# MainBorad_ver2_1.net
KiCad netlist of a schematic drawn in EAGLE
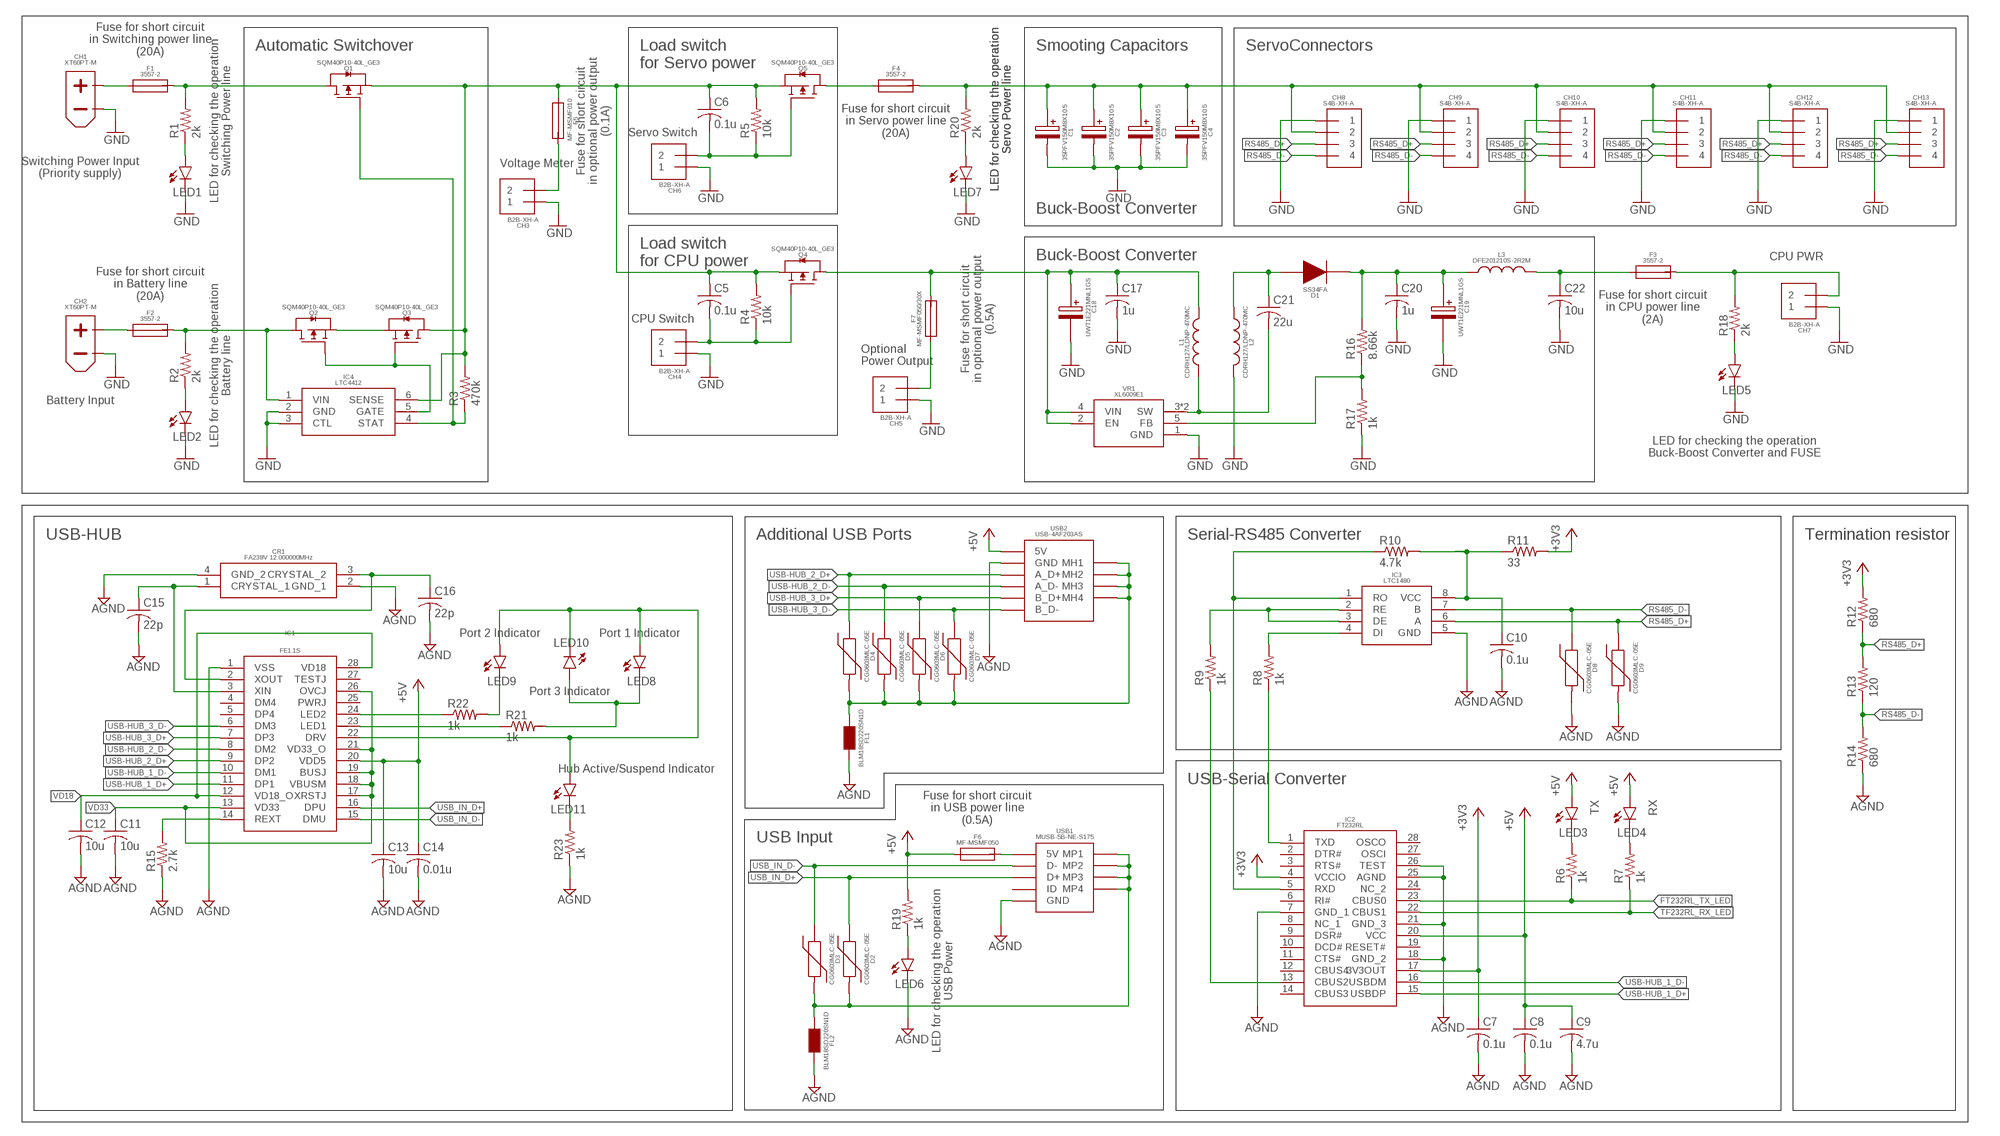
[diagram p0: schematic, sheet 1]

(export (version "E")
  (design (tool "Eeschema 10.0.6"))
  (components
    (comp (ref "C1")
      (value "35PFV150M8X10.5")
      (footprint "eagle-import:35PFV150M8X10.5")
      (libsource (lib "eagle-import") (part "35PFV150M8X10.5"))
    )
    (comp (ref "C2")
      (value "35PFV150M8X10.5")
      (footprint "eagle-import:35PFV150M8X10.5")
      (libsource (lib "eagle-import") (part "35PFV150M8X10.5"))
    )
    (comp (ref "C3")
      (value "35PFV150M8X10.5")
      (footprint "eagle-import:35PFV150M8X10.5")
      (libsource (lib "eagle-import") (part "35PFV150M8X10.5"))
    )
    (comp (ref "C4")
      (value "35PFV150M8X10.5")
      (footprint "eagle-import:35PFV150M8X10.5")
      (libsource (lib "eagle-import") (part "35PFV150M8X10.5"))
    )
    (comp (ref "C5")
      (value "0.1u")
      (footprint "eagle-import:C0603")
      (libsource (lib "eagle-import") (part "C-USC0603"))
    )
    (comp (ref "C6")
      (value "0.1u")
      (footprint "eagle-import:C0603")
      (libsource (lib "eagle-import") (part "C-USC0603"))
    )
    (comp (ref "C7")
      (value "0.1u")
      (footprint "eagle-import:C0603")
      (libsource (lib "eagle-import") (part "C-USC0603"))
    )
    (comp (ref "C8")
      (value "0.1u")
      (footprint "eagle-import:C0603")
      (libsource (lib "eagle-import") (part "C-USC0603"))
    )
    (comp (ref "C9")
      (value "4.7u")
      (footprint "eagle-import:C0603")
      (libsource (lib "eagle-import") (part "C-USC0603"))
    )
    (comp (ref "C10")
      (value "0.1u")
      (footprint "eagle-import:C0603")
      (libsource (lib "eagle-import") (part "C-USC0603"))
    )
    (comp (ref "C11")
      (value "10u")
      (footprint "eagle-import:C0603")
      (libsource (lib "eagle-import") (part "C-USC0603"))
    )
    (comp (ref "C12")
      (value "10u")
      (footprint "eagle-import:C0603")
      (libsource (lib "eagle-import") (part "C-USC0603"))
    )
    (comp (ref "C13")
      (value "10u")
      (footprint "eagle-import:C0603")
      (libsource (lib "eagle-import") (part "C-USC0603"))
    )
    (comp (ref "C14")
      (value "0.01u")
      (footprint "eagle-import:C0603")
      (libsource (lib "eagle-import") (part "C-USC0603"))
    )
    (comp (ref "C15")
      (value "22p")
      (footprint "eagle-import:C0603")
      (libsource (lib "eagle-import") (part "C-USC0603"))
    )
    (comp (ref "C16")
      (value "22p")
      (footprint "eagle-import:C0603")
      (libsource (lib "eagle-import") (part "C-USC0603"))
    )
    (comp (ref "C17")
      (value "1u")
      (footprint "eagle-import:C0603")
      (libsource (lib "eagle-import") (part "C-USC0603"))
    )
    (comp (ref "C18")
      (value "UWT1E221MNL1GS")
      (footprint "eagle-import:UWT1E221MNL1GS")
      (libsource (lib "eagle-import") (part "UWT1E221MNL1GS"))
    )
    (comp (ref "C19")
      (value "UWT1E221MNL1GS")
      (footprint "eagle-import:UWT1E221MNL1GS")
      (libsource (lib "eagle-import") (part "UWT1E221MNL1GS"))
    )
    (comp (ref "C20")
      (value "1u")
      (footprint "eagle-import:C0603")
      (libsource (lib "eagle-import") (part "C-USC0603"))
    )
    (comp (ref "C21")
      (value "22u")
      (footprint "eagle-import:C2012")
      (libsource (lib "eagle-import") (part "C-USC2012"))
    )
    (comp (ref "C22")
      (value "10u")
      (footprint "eagle-import:C0603")
      (libsource (lib "eagle-import") (part "C-USC0603"))
    )
    (comp (ref "CH1")
      (value "XT60PT-M")
      (footprint "eagle-import:XT60PT-M")
      (libsource (lib "eagle-import") (part "XT60PT-M"))
    )
    (comp (ref "CH2")
      (value "XT60PT-M")
      (footprint "eagle-import:XT60PT-M")
      (libsource (lib "eagle-import") (part "XT60PT-M"))
    )
    (comp (ref "CH3")
      (value "B2B-XH-A")
      (footprint "eagle-import:B2B-XH-A")
      (libsource (lib "eagle-import") (part "B2B-XH-A"))
    )
    (comp (ref "CH4")
      (value "B2B-XH-A")
      (footprint "eagle-import:B2B-XH-A")
      (libsource (lib "eagle-import") (part "B2B-XH-A"))
    )
    (comp (ref "CH5")
      (value "B2B-XH-A")
      (footprint "eagle-import:B2B-XH-A")
      (libsource (lib "eagle-import") (part "B2B-XH-A"))
    )
    (comp (ref "CH6")
      (value "B2B-XH-A")
      (footprint "eagle-import:B2B-XH-A")
      (libsource (lib "eagle-import") (part "B2B-XH-A"))
    )
    (comp (ref "CH7")
      (value "B2B-XH-A")
      (footprint "eagle-import:B2B-XH-A")
      (libsource (lib "eagle-import") (part "B2B-XH-A"))
    )
    (comp (ref "CH8")
      (value "S4B-XH-A")
      (footprint "eagle-import:S4B-XH-A")
      (libsource (lib "eagle-import") (part "S4B-XH-A"))
    )
    (comp (ref "CH9")
      (value "S4B-XH-A")
      (footprint "eagle-import:S4B-XH-A")
      (libsource (lib "eagle-import") (part "S4B-XH-A"))
    )
    (comp (ref "CH10")
      (value "S4B-XH-A")
      (footprint "eagle-import:S4B-XH-A")
      (libsource (lib "eagle-import") (part "S4B-XH-A"))
    )
    (comp (ref "CH11")
      (value "S4B-XH-A")
      (footprint "eagle-import:S4B-XH-A")
      (libsource (lib "eagle-import") (part "S4B-XH-A"))
    )
    (comp (ref "CH12")
      (value "S4B-XH-A")
      (footprint "eagle-import:S4B-XH-A")
      (libsource (lib "eagle-import") (part "S4B-XH-A"))
    )
    (comp (ref "CH13")
      (value "S4B-XH-A")
      (footprint "eagle-import:S4B-XH-A")
      (libsource (lib "eagle-import") (part "S4B-XH-A"))
    )
    (comp (ref "CR1")
      (value "FA238V_12.000000MHZ")
      (footprint "eagle-import:FA238V")
      (libsource (lib "eagle-import") (part "FA238V_12.000000MHZ"))
    )
    (comp (ref "D1")
      (value "SS34FA")
      (footprint "eagle-import:SS34FA")
      (libsource (lib "eagle-import") (part "SS34FA"))
    )
    (comp (ref "D2")
      (value "CG0603MLC-05E")
      (footprint "eagle-import:CG0603MLC-05E")
      (libsource (lib "eagle-import") (part "CG0603MLC-05E"))
    )
    (comp (ref "D3")
      (value "CG0603MLC-05E")
      (footprint "eagle-import:CG0603MLC-05E")
      (libsource (lib "eagle-import") (part "CG0603MLC-05E"))
    )
    (comp (ref "D4")
      (value "CG0603MLC-05E")
      (footprint "eagle-import:CG0603MLC-05E")
      (libsource (lib "eagle-import") (part "CG0603MLC-05E"))
    )
    (comp (ref "D5")
      (value "CG0603MLC-05E")
      (footprint "eagle-import:CG0603MLC-05E")
      (libsource (lib "eagle-import") (part "CG0603MLC-05E"))
    )
    (comp (ref "D6")
      (value "CG0603MLC-05E")
      (footprint "eagle-import:CG0603MLC-05E")
      (libsource (lib "eagle-import") (part "CG0603MLC-05E"))
    )
    (comp (ref "D7")
      (value "CG0603MLC-05E")
      (footprint "eagle-import:CG0603MLC-05E")
      (libsource (lib "eagle-import") (part "CG0603MLC-05E"))
    )
    (comp (ref "D8")
      (value "CG0603MLC-05E")
      (footprint "eagle-import:CG0603MLC-05E")
      (libsource (lib "eagle-import") (part "CG0603MLC-05E"))
    )
    (comp (ref "D9")
      (value "CG0603MLC-05E")
      (footprint "eagle-import:CG0603MLC-05E")
      (libsource (lib "eagle-import") (part "CG0603MLC-05E"))
    )
    (comp (ref "F1")
      (value "3557-2")
      (footprint "eagle-import:3557-2")
      (libsource (lib "eagle-import") (part "3557-2"))
    )
    (comp (ref "F2")
      (value "3557-2")
      (footprint "eagle-import:3557-2")
      (libsource (lib "eagle-import") (part "3557-2"))
    )
    (comp (ref "F3")
      (value "3557-2")
      (footprint "eagle-import:3557-2")
      (libsource (lib "eagle-import") (part "3557-2"))
    )
    (comp (ref "F4")
      (value "3557-2")
      (footprint "eagle-import:3557-2")
      (libsource (lib "eagle-import") (part "3557-2"))
    )
    (comp (ref "F5")
      (value "MF-MSMF010")
      (footprint "eagle-import:MF-MSMF010")
      (libsource (lib "eagle-import") (part "MF-MSMF010"))
    )
    (comp (ref "F6")
      (value "MF-MSMF050")
      (footprint "eagle-import:MF-MSMF050")
      (libsource (lib "eagle-import") (part "MF-MSMF050"))
    )
    (comp (ref "F7")
      (value "MF-MSMF050/30X")
      (footprint "eagle-import:MF-MSMF050")
      (libsource (lib "eagle-import") (part "MF-MSMF050/30X"))
    )
    (comp (ref "FL1")
      (value "BLM18SD220SN1D")
      (footprint "eagle-import:BLM18SD220SN1D")
      (libsource (lib "eagle-import") (part "BLM18SD220SN1D"))
    )
    (comp (ref "FL2")
      (value "BLM18SD220SN1D")
      (footprint "eagle-import:BLM18SD220SN1D")
      (libsource (lib "eagle-import") (part "BLM18SD220SN1D"))
    )
    (comp (ref "IC1")
      (value "FE1.1S")
      (footprint "eagle-import:FE1.1S")
      (libsource (lib "eagle-import") (part "FE1.1S"))
    )
    (comp (ref "IC2")
      (value "FT232RL")
      (footprint "eagle-import:FT232RL")
      (libsource (lib "eagle-import") (part "FT232RL"))
    )
    (comp (ref "IC3")
      (value "LTC1480")
      (footprint "eagle-import:LTC1480")
      (libsource (lib "eagle-import") (part "LTC1480"))
    )
    (comp (ref "IC4")
      (value "LTC4412")
      (footprint "eagle-import:LTC4412")
      (libsource (lib "eagle-import") (part "LTC4412"))
    )
    (comp (ref "L1")
      (value "CDRH127/LDNP-470MC")
      (footprint "eagle-import:CDRH127_LDNP")
      (libsource (lib "eagle-import") (part "CDRH127/LDNP-470MC"))
    )
    (comp (ref "L2")
      (value "CDRH127/LDNP-470MC")
      (footprint "eagle-import:CDRH127_LDNP")
      (libsource (lib "eagle-import") (part "CDRH127/LDNP-470MC"))
    )
    (comp (ref "L3")
      (value "DFE201210S-2R2M")
      (footprint "eagle-import:DFE201210S")
      (libsource (lib "eagle-import") (part "DFE201210S-2R2M"))
    )
    (comp (ref "LED1")
      (value "LEDSML0603")
      (footprint "eagle-import:SML0603")
      (libsource (lib "eagle-import") (part "LEDSML0603"))
    )
    (comp (ref "LED2")
      (value "LEDSML0603")
      (footprint "eagle-import:SML0603")
      (libsource (lib "eagle-import") (part "LEDSML0603"))
    )
    (comp (ref "LED3")
      (value "LEDSML0603")
      (footprint "eagle-import:SML0603")
      (libsource (lib "eagle-import") (part "LEDSML0603"))
    )
    (comp (ref "LED4")
      (value "LEDSML0603")
      (footprint "eagle-import:SML0603")
      (libsource (lib "eagle-import") (part "LEDSML0603"))
    )
    (comp (ref "LED5")
      (value "LEDSML0603")
      (footprint "eagle-import:SML0603")
      (libsource (lib "eagle-import") (part "LEDSML0603"))
    )
    (comp (ref "LED6")
      (value "LEDSML0603")
      (footprint "eagle-import:SML0603")
      (libsource (lib "eagle-import") (part "LEDSML0603"))
    )
    (comp (ref "LED7")
      (value "LEDSML0603")
      (footprint "eagle-import:SML0603")
      (libsource (lib "eagle-import") (part "LEDSML0603"))
    )
    (comp (ref "LED8")
      (value "LEDSML0603")
      (footprint "eagle-import:SML0603")
      (libsource (lib "eagle-import") (part "LEDSML0603"))
    )
    (comp (ref "LED9")
      (value "LEDSML0603")
      (footprint "eagle-import:SML0603")
      (libsource (lib "eagle-import") (part "LEDSML0603"))
    )
    (comp (ref "LED10")
      (value "LEDSML0603")
      (footprint "eagle-import:SML0603")
      (libsource (lib "eagle-import") (part "LEDSML0603"))
    )
    (comp (ref "LED11")
      (value "LEDSML0603")
      (footprint "eagle-import:SML0603")
      (libsource (lib "eagle-import") (part "LEDSML0603"))
    )
    (comp (ref "Q1")
      (value "SQM40P10-40L_GE3")
      (footprint "eagle-import:TO-252-3")
      (libsource (lib "eagle-import") (part "SQM40P10-40L_GE3"))
    )
    (comp (ref "Q2")
      (value "SQM40P10-40L_GE3")
      (footprint "eagle-import:TO-252-3")
      (libsource (lib "eagle-import") (part "SQM40P10-40L_GE3"))
    )
    (comp (ref "Q3")
      (value "SQM40P10-40L_GE3")
      (footprint "eagle-import:TO-252-3")
      (libsource (lib "eagle-import") (part "SQM40P10-40L_GE3"))
    )
    (comp (ref "Q4")
      (value "SQM40P10-40L_GE3")
      (footprint "eagle-import:TO-252-3")
      (libsource (lib "eagle-import") (part "SQM40P10-40L_GE3"))
    )
    (comp (ref "Q5")
      (value "SQM40P10-40L_GE3")
      (footprint "eagle-import:TO-252-3")
      (libsource (lib "eagle-import") (part "SQM40P10-40L_GE3"))
    )
    (comp (ref "R1")
      (value "2k")
      (footprint "eagle-import:R0603")
      (libsource (lib "eagle-import") (part "R-US_R0603"))
    )
    (comp (ref "R2")
      (value "2k")
      (footprint "eagle-import:R0603")
      (libsource (lib "eagle-import") (part "R-US_R0603"))
    )
    (comp (ref "R3")
      (value "470k")
      (footprint "eagle-import:R0603")
      (libsource (lib "eagle-import") (part "R-US_R0603"))
    )
    (comp (ref "R4")
      (value "10k")
      (footprint "eagle-import:R0603")
      (libsource (lib "eagle-import") (part "R-US_R0603"))
    )
    (comp (ref "R5")
      (value "10k")
      (footprint "eagle-import:R0603")
      (libsource (lib "eagle-import") (part "R-US_R0603"))
    )
    (comp (ref "R6")
      (value "1k")
      (footprint "eagle-import:R0603")
      (libsource (lib "eagle-import") (part "R-US_R0603"))
    )
    (comp (ref "R7")
      (value "1k")
      (footprint "eagle-import:R0603")
      (libsource (lib "eagle-import") (part "R-US_R0603"))
    )
    (comp (ref "R8")
      (value "1k")
      (footprint "eagle-import:R0603")
      (libsource (lib "eagle-import") (part "R-US_R0603"))
    )
    (comp (ref "R9")
      (value "1k")
      (footprint "eagle-import:R0603")
      (libsource (lib "eagle-import") (part "R-US_R0603"))
    )
    (comp (ref "R10")
      (value "4.7k")
      (footprint "eagle-import:R0603")
      (libsource (lib "eagle-import") (part "R-US_R0603"))
    )
    (comp (ref "R11")
      (value "33")
      (footprint "eagle-import:R0603")
      (libsource (lib "eagle-import") (part "R-US_R0603"))
    )
    (comp (ref "R12")
      (value "680")
      (footprint "eagle-import:R0603")
      (libsource (lib "eagle-import") (part "R-US_R0603"))
    )
    (comp (ref "R13")
      (value "120")
      (footprint "eagle-import:R0603")
      (libsource (lib "eagle-import") (part "R-US_R0603"))
    )
    (comp (ref "R14")
      (value "680")
      (footprint "eagle-import:R0603")
      (libsource (lib "eagle-import") (part "R-US_R0603"))
    )
    (comp (ref "R15")
      (value "2.7k")
      (footprint "eagle-import:R0603")
      (libsource (lib "eagle-import") (part "R-US_R0603"))
    )
    (comp (ref "R16")
      (value "8.66k")
      (footprint "eagle-import:R0603")
      (libsource (lib "eagle-import") (part "R-US_R0603"))
    )
    (comp (ref "R17")
      (value "1k")
      (footprint "eagle-import:R0603")
      (libsource (lib "eagle-import") (part "R-US_R0603"))
    )
    (comp (ref "R18")
      (value "2k")
      (footprint "eagle-import:R0603")
      (libsource (lib "eagle-import") (part "R-US_R0603"))
    )
    (comp (ref "R19")
      (value "1k")
      (footprint "eagle-import:R0603")
      (libsource (lib "eagle-import") (part "R-US_R0603"))
    )
    (comp (ref "R20")
      (value "2k")
      (footprint "eagle-import:R0603")
      (libsource (lib "eagle-import") (part "R-US_R0603"))
    )
    (comp (ref "R21")
      (value "1k")
      (footprint "eagle-import:R0603")
      (libsource (lib "eagle-import") (part "R-US_R0603"))
    )
    (comp (ref "R22")
      (value "1k")
      (footprint "eagle-import:R0603")
      (libsource (lib "eagle-import") (part "R-US_R0603"))
    )
    (comp (ref "R23")
      (value "1k")
      (footprint "eagle-import:R0603")
      (libsource (lib "eagle-import") (part "R-US_R0603"))
    )
    (comp (ref "USB1")
      (value "MINI_USB_5P_B_TYPE")
      (footprint "eagle-import:MINI_USB_5P_B_TYPE")
      (libsource (lib "eagle-import") (part "MINI_USB_5P_B_TYPE"))
    )
    (comp (ref "USB2")
      (value "USB_4P_A_TYPE_X2")
      (footprint "eagle-import:USB_4P_A_TYPE_X2")
      (libsource (lib "eagle-import") (part "USB_4P_A_TYPE_X2"))
    )
    (comp (ref "VR1")
      (value "XL6009E1")
      (footprint "eagle-import:TO263-5L")
      (libsource (lib "eagle-import") (part "XL6009E1"))
    )
  )
  (nets
    (net (code "1") (name "+3V3") (class "Default")
      (node (ref "C7") (pin "1") (pinfunction "1_1") (pintype "passive"))
      (node (ref "IC2") (pin "17") (pinfunction "3V3OUT_17") (pintype "bidirectional"))
      (node (ref "IC2") (pin "4") (pinfunction "VCCIO_4") (pintype "bidirectional"))
      (node (ref "R11") (pin "2") (pinfunction "2_2") (pintype "passive"))
      (node (ref "R12") (pin "2") (pinfunction "2_2") (pintype "passive"))
    )
    (net (code "2") (name "+5V") (class "Default")
      (node (ref "C13") (pin "1") (pinfunction "1_1") (pintype "passive"))
      (node (ref "C14") (pin "1") (pinfunction "1_1") (pintype "passive"))
      (node (ref "C8") (pin "1") (pinfunction "1_1") (pintype "passive"))
      (node (ref "C9") (pin "1") (pinfunction "1_1") (pintype "passive"))
      (node (ref "F6") (pin "1") (pinfunction "1_1") (pintype "bidirectional"))
      (node (ref "IC1") (pin "20") (pinfunction "VDD5_20") (pintype "bidirectional"))
      (node (ref "IC2") (pin "20") (pinfunction "VCC_20") (pintype "bidirectional"))
      (node (ref "LED3") (pin "A") (pinfunction "A_A") (pintype "passive"))
      (node (ref "LED4") (pin "A") (pinfunction "A_A") (pintype "passive"))
      (node (ref "R19") (pin "2") (pinfunction "2_2") (pintype "passive"))
      (node (ref "USB2") (pin "4") (pinfunction "5V_4") (pintype "bidirectional"))
      (node (ref "USB2") (pin "8") (pinfunction "5V_8") (pintype "bidirectional"))
    )
    (net (code "3") (name "AGND") (class "Default")
      (node (ref "C10") (pin "2") (pinfunction "2_2") (pintype "passive"))
      (node (ref "C11") (pin "2") (pinfunction "2_2") (pintype "passive"))
      (node (ref "C12") (pin "2") (pinfunction "2_2") (pintype "passive"))
      (node (ref "C13") (pin "2") (pinfunction "2_2") (pintype "passive"))
      (node (ref "C14") (pin "2") (pinfunction "2_2") (pintype "passive"))
      (node (ref "C15") (pin "2") (pinfunction "2_2") (pintype "passive"))
      (node (ref "C16") (pin "2") (pinfunction "2_2") (pintype "passive"))
      (node (ref "C7") (pin "2") (pinfunction "2_2") (pintype "passive"))
      (node (ref "C8") (pin "2") (pinfunction "2_2") (pintype "passive"))
      (node (ref "C9") (pin "2") (pinfunction "2_2") (pintype "passive"))
      (node (ref "CR1") (pin "2") (pinfunction "GND_1_2") (pintype "bidirectional"))
      (node (ref "CR1") (pin "4") (pinfunction "GND_2_4") (pintype "bidirectional"))
      (node (ref "D8") (pin "2") (pinfunction "2_2") (pintype "bidirectional"))
      (node (ref "D9") (pin "2") (pinfunction "2_2") (pintype "bidirectional"))
      (node (ref "FL1") (pin "2") (pinfunction "2_2") (pintype "bidirectional"))
      (node (ref "FL2") (pin "2") (pinfunction "2_2") (pintype "bidirectional"))
      (node (ref "IC1") (pin "1") (pinfunction "VSS_1") (pintype "bidirectional"))
      (node (ref "IC2") (pin "18") (pinfunction "GND_2_18") (pintype "bidirectional"))
      (node (ref "IC2") (pin "21") (pinfunction "GND_3_21") (pintype "bidirectional"))
      (node (ref "IC2") (pin "25") (pinfunction "AGND_25") (pintype "bidirectional"))
      (node (ref "IC2") (pin "26") (pinfunction "TEST_26") (pintype "bidirectional"))
      (node (ref "IC2") (pin "7") (pinfunction "GND_1_7") (pintype "bidirectional"))
      (node (ref "IC3") (pin "5") (pinfunction "GND_5") (pintype "bidirectional"))
      (node (ref "LED6") (pin "C") (pinfunction "C_C") (pintype "passive"))
      (node (ref "R14") (pin "1") (pinfunction "1_1") (pintype "passive"))
      (node (ref "R15") (pin "1") (pinfunction "1_1") (pintype "passive"))
      (node (ref "R23") (pin "1") (pinfunction "1_1") (pintype "passive"))
      (node (ref "USB1") (pin "5") (pinfunction "GND_5") (pintype "bidirectional"))
      (node (ref "USB2") (pin "1") (pinfunction "GND_1") (pintype "bidirectional"))
      (node (ref "USB2") (pin "5") (pinfunction "GND_5") (pintype "bidirectional"))
    )
    (net (code "4") (name "FT232RL_TX_LED") (class "Default")
      (node (ref "IC2") (pin "23") (pinfunction "CBUS0_23") (pintype "bidirectional"))
      (node (ref "R6") (pin "1") (pinfunction "1_1") (pintype "passive"))
    )
    (net (code "5") (name "GND") (class "Default")
      (node (ref "C1") (pin "-") (pinfunction "-_-") (pintype "bidirectional"))
      (node (ref "C17") (pin "2") (pinfunction "2_2") (pintype "passive"))
      (node (ref "C18") (pin "-") (pinfunction "-_-") (pintype "bidirectional"))
      (node (ref "C19") (pin "-") (pinfunction "-_-") (pintype "bidirectional"))
      (node (ref "C2") (pin "-") (pinfunction "-_-") (pintype "bidirectional"))
      (node (ref "C20") (pin "2") (pinfunction "2_2") (pintype "passive"))
      (node (ref "C22") (pin "2") (pinfunction "2_2") (pintype "passive"))
      (node (ref "C3") (pin "-") (pinfunction "-_-") (pintype "bidirectional"))
      (node (ref "C4") (pin "-") (pinfunction "-_-") (pintype "bidirectional"))
      (node (ref "CH1") (pin "-") (pinfunction "-_-") (pintype "power_in"))
      (node (ref "CH10") (pin "1") (pinfunction "1_1") (pintype "bidirectional"))
      (node (ref "CH11") (pin "1") (pinfunction "1_1") (pintype "bidirectional"))
      (node (ref "CH12") (pin "1") (pinfunction "1_1") (pintype "bidirectional"))
      (node (ref "CH13") (pin "1") (pinfunction "1_1") (pintype "bidirectional"))
      (node (ref "CH2") (pin "-") (pinfunction "-_-") (pintype "power_in"))
      (node (ref "CH3") (pin "1") (pinfunction "1_1") (pintype "bidirectional"))
      (node (ref "CH4") (pin "1") (pinfunction "1_1") (pintype "bidirectional"))
      (node (ref "CH5") (pin "1") (pinfunction "1_1") (pintype "bidirectional"))
      (node (ref "CH6") (pin "1") (pinfunction "1_1") (pintype "bidirectional"))
      (node (ref "CH7") (pin "1") (pinfunction "1_1") (pintype "bidirectional"))
      (node (ref "CH8") (pin "1") (pinfunction "1_1") (pintype "bidirectional"))
      (node (ref "CH9") (pin "1") (pinfunction "1_1") (pintype "bidirectional"))
      (node (ref "IC4") (pin "2") (pinfunction "GND_2") (pintype "bidirectional"))
      (node (ref "IC4") (pin "3") (pinfunction "CTL_3") (pintype "bidirectional"))
      (node (ref "L2") (pin "2") (pinfunction "2_2") (pintype "bidirectional"))
      (node (ref "LED1") (pin "C") (pinfunction "C_C") (pintype "passive"))
      (node (ref "LED2") (pin "C") (pinfunction "C_C") (pintype "passive"))
      (node (ref "LED5") (pin "C") (pinfunction "C_C") (pintype "passive"))
      (node (ref "LED7") (pin "C") (pinfunction "C_C") (pintype "passive"))
      (node (ref "R17") (pin "1") (pinfunction "1_1") (pintype "passive"))
      (node (ref "VR1") (pin "1") (pinfunction "GND_1") (pintype "power_in"))
    )
    (net (code "6") (name "Net-(C1-Pad+)") (class "Default")
      (node (ref "C1") (pin "+") (pinfunction "+_+") (pintype "bidirectional"))
      (node (ref "C2") (pin "+") (pinfunction "+_+") (pintype "bidirectional"))
      (node (ref "C3") (pin "+") (pinfunction "+_+") (pintype "bidirectional"))
      (node (ref "C4") (pin "+") (pinfunction "+_+") (pintype "bidirectional"))
      (node (ref "CH10") (pin "2") (pinfunction "2_2") (pintype "bidirectional"))
      (node (ref "CH11") (pin "2") (pinfunction "2_2") (pintype "bidirectional"))
      (node (ref "CH12") (pin "2") (pinfunction "2_2") (pintype "bidirectional"))
      (node (ref "CH13") (pin "2") (pinfunction "2_2") (pintype "bidirectional"))
      (node (ref "CH8") (pin "2") (pinfunction "2_2") (pintype "bidirectional"))
      (node (ref "CH9") (pin "2") (pinfunction "2_2") (pintype "bidirectional"))
      (node (ref "F4") (pin "3") (pinfunction "2_3") (pintype "bidirectional"))
      (node (ref "F4") (pin "4") (pinfunction "2_4") (pintype "bidirectional"))
      (node (ref "R20") (pin "2") (pinfunction "2_2") (pintype "passive"))
    )
    (net (code "7") (name "Net-(C21-Pad1)") (class "Default")
      (node (ref "C21") (pin "1") (pinfunction "1_1") (pintype "passive"))
      (node (ref "D1") (pin "2") (pinfunction "2_2") (pintype "bidirectional"))
      (node (ref "L2") (pin "1") (pinfunction "1_1") (pintype "bidirectional"))
    )
    (net (code "8") (name "Net-(C21-Pad2)") (class "Default")
      (node (ref "C21") (pin "2") (pinfunction "2_2") (pintype "passive"))
      (node (ref "L1") (pin "1") (pinfunction "1_1") (pintype "bidirectional"))
      (node (ref "VR1") (pin "3") (pinfunction "SW_3") (pintype "output"))
      (node (ref "VR1") (pin "6") (pinfunction "SW_6") (pintype "output"))
    )
    (net (code "9") (name "Net-(CH1-Pad+)") (class "Default")
      (node (ref "CH1") (pin "+") (pinfunction "+_+") (pintype "power_in"))
      (node (ref "F1") (pin "1") (pinfunction "1_1") (pintype "bidirectional"))
      (node (ref "F1") (pin "2") (pinfunction "1_2") (pintype "bidirectional"))
    )
    (net (code "10") (name "Net-(CH2-Pad+)") (class "Default")
      (node (ref "CH2") (pin "+") (pinfunction "+_+") (pintype "power_in"))
      (node (ref "F2") (pin "1") (pinfunction "1_1") (pintype "bidirectional"))
      (node (ref "F2") (pin "2") (pinfunction "1_2") (pintype "bidirectional"))
    )
    (net (code "11") (name "Net-(CH3-Pad2)") (class "Default")
      (node (ref "CH3") (pin "2") (pinfunction "2_2") (pintype "bidirectional"))
      (node (ref "F5") (pin "2") (pinfunction "2_2") (pintype "bidirectional"))
    )
    (net (code "12") (name "Net-(CH5-Pad2)") (class "Default")
      (node (ref "CH5") (pin "2") (pinfunction "2_2") (pintype "bidirectional"))
      (node (ref "F7") (pin "1") (pinfunction "1_1") (pintype "bidirectional"))
    )
    (net (code "13") (name "Net-(CH7-Pad2)") (class "Default")
      (node (ref "CH7") (pin "2") (pinfunction "2_2") (pintype "bidirectional"))
      (node (ref "F3") (pin "3") (pinfunction "2_3") (pintype "bidirectional"))
      (node (ref "F3") (pin "4") (pinfunction "2_4") (pintype "bidirectional"))
      (node (ref "R18") (pin "2") (pinfunction "2_2") (pintype "passive"))
    )
    (net (code "14") (name "Net-(CR1-CRYSTAL_1)") (class "Default")
      (node (ref "C15") (pin "1") (pinfunction "1_1") (pintype "passive"))
      (node (ref "CR1") (pin "1") (pinfunction "CRYSTAL_1_1") (pintype "bidirectional"))
      (node (ref "IC1") (pin "3") (pinfunction "XIN_3") (pintype "bidirectional"))
    )
    (net (code "15") (name "Net-(CR1-CRYSTAL_2)") (class "Default")
      (node (ref "C16") (pin "1") (pinfunction "1_1") (pintype "passive"))
      (node (ref "CR1") (pin "3") (pinfunction "CRYSTAL_2_3") (pintype "bidirectional"))
      (node (ref "IC1") (pin "2") (pinfunction "XOUT_2") (pintype "bidirectional"))
    )
    (net (code "16") (name "Net-(D2-Pad2)") (class "Default")
      (node (ref "D2") (pin "2") (pinfunction "2_2") (pintype "bidirectional"))
      (node (ref "D3") (pin "2") (pinfunction "2_2") (pintype "bidirectional"))
      (node (ref "FL2") (pin "1") (pinfunction "1_1") (pintype "bidirectional"))
      (node (ref "USB1") (pin "MP1") (pinfunction "MP1_MP1") (pintype "bidirectional"))
      (node (ref "USB1") (pin "MP2") (pinfunction "MP2_MP2") (pintype "bidirectional"))
      (node (ref "USB1") (pin "MP3") (pinfunction "MP3_MP3") (pintype "bidirectional"))
      (node (ref "USB1") (pin "MP4") (pinfunction "MP4_MP4") (pintype "bidirectional"))
    )
    (net (code "17") (name "Net-(D4-Pad2)") (class "Default")
      (node (ref "D4") (pin "2") (pinfunction "2_2") (pintype "bidirectional"))
      (node (ref "D5") (pin "2") (pinfunction "2_2") (pintype "bidirectional"))
      (node (ref "D6") (pin "2") (pinfunction "2_2") (pintype "bidirectional"))
      (node (ref "D7") (pin "2") (pinfunction "2_2") (pintype "bidirectional"))
      (node (ref "FL1") (pin "1") (pinfunction "1_1") (pintype "bidirectional"))
      (node (ref "USB2") (pin "MH1") (pinfunction "MH1_MH1") (pintype "bidirectional"))
      (node (ref "USB2") (pin "MH2") (pinfunction "MH2_MH2") (pintype "bidirectional"))
      (node (ref "USB2") (pin "MH3") (pinfunction "MH3_MH3") (pintype "bidirectional"))
      (node (ref "USB2") (pin "MH4") (pinfunction "MH4_MH4") (pintype "bidirectional"))
    )
    (net (code "18") (name "Net-(IC1-DRV)") (class "Default")
      (node (ref "IC1") (pin "22") (pinfunction "DRV_22") (pintype "bidirectional"))
      (node (ref "LED10") (pin "C") (pinfunction "C_C") (pintype "passive"))
      (node (ref "LED11") (pin "A") (pinfunction "A_A") (pintype "passive"))
      (node (ref "LED8") (pin "A") (pinfunction "A_A") (pintype "passive"))
      (node (ref "LED9") (pin "A") (pinfunction "A_A") (pintype "passive"))
    )
    (net (code "19") (name "Net-(IC1-LED1)") (class "Default")
      (node (ref "IC1") (pin "23") (pinfunction "LED1_23") (pintype "bidirectional"))
      (node (ref "R21") (pin "1") (pinfunction "1_1") (pintype "passive"))
    )
    (net (code "20") (name "Net-(IC1-LED2)") (class "Default")
      (node (ref "IC1") (pin "24") (pinfunction "LED2_24") (pintype "bidirectional"))
      (node (ref "R22") (pin "1") (pinfunction "1_1") (pintype "passive"))
    )
    (net (code "21") (name "Net-(IC1-REXT)") (class "Default")
      (node (ref "IC1") (pin "14") (pinfunction "REXT_14") (pintype "bidirectional"))
      (node (ref "R15") (pin "2") (pinfunction "2_2") (pintype "passive"))
    )
    (net (code "22") (name "Net-(IC2-CBUS2)") (class "Default")
      (node (ref "IC2") (pin "13") (pinfunction "CBUS2_13") (pintype "bidirectional"))
      (node (ref "R9") (pin "1") (pinfunction "1_1") (pintype "passive"))
    )
    (net (code "23") (name "Net-(IC2-RXD)") (class "Default")
      (node (ref "IC2") (pin "5") (pinfunction "RXD_5") (pintype "bidirectional"))
      (node (ref "IC3") (pin "1") (pinfunction "RO_1") (pintype "bidirectional"))
      (node (ref "R10") (pin "1") (pinfunction "1_1") (pintype "passive"))
    )
    (net (code "24") (name "Net-(IC2-TXD)") (class "Default")
      (node (ref "IC2") (pin "1") (pinfunction "TXD_1") (pintype "bidirectional"))
      (node (ref "R8") (pin "1") (pinfunction "1_1") (pintype "passive"))
    )
    (net (code "25") (name "Net-(IC3-DE)") (class "Default")
      (node (ref "IC3") (pin "2") (pinfunction "RE_2") (pintype "bidirectional"))
      (node (ref "IC3") (pin "3") (pinfunction "DE_3") (pintype "bidirectional"))
      (node (ref "R9") (pin "2") (pinfunction "2_2") (pintype "passive"))
    )
    (net (code "26") (name "Net-(IC3-DI)") (class "Default")
      (node (ref "IC3") (pin "4") (pinfunction "DI_4") (pintype "bidirectional"))
      (node (ref "R8") (pin "2") (pinfunction "2_2") (pintype "passive"))
    )
    (net (code "27") (name "Net-(IC3-VCC)") (class "Default")
      (node (ref "C10") (pin "1") (pinfunction "1_1") (pintype "passive"))
      (node (ref "IC3") (pin "8") (pinfunction "VCC_8") (pintype "bidirectional"))
      (node (ref "R10") (pin "2") (pinfunction "2_2") (pintype "passive"))
      (node (ref "R11") (pin "1") (pinfunction "1_1") (pintype "passive"))
    )
    (net (code "28") (name "Net-(IC4-GATE)") (class "Default")
      (node (ref "IC4") (pin "5") (pinfunction "GATE_5") (pintype "bidirectional"))
      (node (ref "Q2") (pin "1") (pinfunction "G_1") (pintype "bidirectional"))
      (node (ref "Q3") (pin "1") (pinfunction "G_1") (pintype "bidirectional"))
    )
    (net (code "29") (name "Net-(IC4-SENSE)") (class "Default")
      (node (ref "C5") (pin "1") (pinfunction "1_1") (pintype "passive"))
      (node (ref "C6") (pin "1") (pinfunction "1_1") (pintype "passive"))
      (node (ref "F5") (pin "1") (pinfunction "1_1") (pintype "bidirectional"))
      (node (ref "IC4") (pin "6") (pinfunction "SENSE_6") (pintype "bidirectional"))
      (node (ref "Q1") (pin "3") (pinfunction "S_3") (pintype "bidirectional"))
      (node (ref "Q3") (pin "4") (pinfunction "D_4") (pintype "bidirectional"))
      (node (ref "Q4") (pin "3") (pinfunction "S_3") (pintype "bidirectional"))
      (node (ref "Q5") (pin "3") (pinfunction "S_3") (pintype "bidirectional"))
      (node (ref "R3") (pin "2") (pinfunction "2_2") (pintype "passive"))
      (node (ref "R4") (pin "2") (pinfunction "2_2") (pintype "passive"))
      (node (ref "R5") (pin "2") (pinfunction "2_2") (pintype "passive"))
    )
    (net (code "30") (name "Net-(IC4-STAT)") (class "Default")
      (node (ref "IC4") (pin "4") (pinfunction "STAT_4") (pintype "bidirectional"))
      (node (ref "Q1") (pin "1") (pinfunction "G_1") (pintype "bidirectional"))
      (node (ref "R3") (pin "1") (pinfunction "1_1") (pintype "passive"))
    )
    (net (code "31") (name "Net-(IC4-VIN)") (class "Default")
      (node (ref "F2") (pin "3") (pinfunction "2_3") (pintype "bidirectional"))
      (node (ref "F2") (pin "4") (pinfunction "2_4") (pintype "bidirectional"))
      (node (ref "IC4") (pin "1") (pinfunction "VIN_1") (pintype "bidirectional"))
      (node (ref "Q2") (pin "4") (pinfunction "D_4") (pintype "bidirectional"))
      (node (ref "R2") (pin "2") (pinfunction "2_2") (pintype "passive"))
    )
    (net (code "32") (name "Net-(L3-P$1)") (class "Default")
      (node (ref "C19") (pin "+") (pinfunction "+_+") (pintype "bidirectional"))
      (node (ref "C20") (pin "1") (pinfunction "1_1") (pintype "passive"))
      (node (ref "D1") (pin "1") (pinfunction "1_1") (pintype "bidirectional"))
      (node (ref "L3") (pin "1") (pinfunction "P$1_1") (pintype "bidirectional"))
      (node (ref "R16") (pin "2") (pinfunction "2_2") (pintype "passive"))
    )
    (net (code "33") (name "Net-(L3-P$2)") (class "Default")
      (node (ref "C22") (pin "1") (pinfunction "1_1") (pintype "passive"))
      (node (ref "F3") (pin "1") (pinfunction "1_1") (pintype "bidirectional"))
      (node (ref "F3") (pin "2") (pinfunction "1_2") (pintype "bidirectional"))
      (node (ref "L3") (pin "2") (pinfunction "P$2_2") (pintype "bidirectional"))
    )
    (net (code "34") (name "Net-(LED1-PadA)") (class "Default")
      (node (ref "LED1") (pin "A") (pinfunction "A_A") (pintype "passive"))
      (node (ref "R1") (pin "1") (pinfunction "1_1") (pintype "passive"))
    )
    (net (code "35") (name "Net-(LED2-PadA)") (class "Default")
      (node (ref "LED2") (pin "A") (pinfunction "A_A") (pintype "passive"))
      (node (ref "R2") (pin "1") (pinfunction "1_1") (pintype "passive"))
    )
    (net (code "36") (name "Net-(LED3-PadC)") (class "Default")
      (node (ref "LED3") (pin "C") (pinfunction "C_C") (pintype "passive"))
      (node (ref "R6") (pin "2") (pinfunction "2_2") (pintype "passive"))
    )
    (net (code "37") (name "Net-(LED4-PadC)") (class "Default")
      (node (ref "LED4") (pin "C") (pinfunction "C_C") (pintype "passive"))
      (node (ref "R7") (pin "2") (pinfunction "2_2") (pintype "passive"))
    )
    (net (code "38") (name "Net-(LED5-PadA)") (class "Default")
      (node (ref "LED5") (pin "A") (pinfunction "A_A") (pintype "passive"))
      (node (ref "R18") (pin "1") (pinfunction "1_1") (pintype "passive"))
    )
    (net (code "39") (name "Net-(LED6-PadA)") (class "Default")
      (node (ref "LED6") (pin "A") (pinfunction "A_A") (pintype "passive"))
      (node (ref "R19") (pin "1") (pinfunction "1_1") (pintype "passive"))
    )
    (net (code "40") (name "Net-(LED7-PadA)") (class "Default")
      (node (ref "LED7") (pin "A") (pinfunction "A_A") (pintype "passive"))
      (node (ref "R20") (pin "1") (pinfunction "1_1") (pintype "passive"))
    )
    (net (code "41") (name "Net-(LED9-PadC)") (class "Default")
      (node (ref "LED9") (pin "C") (pinfunction "C_C") (pintype "passive"))
      (node (ref "R22") (pin "2") (pinfunction "2_2") (pintype "passive"))
    )
    (net (code "42") (name "Net-(LED10-PadA)") (class "Default")
      (node (ref "LED10") (pin "A") (pinfunction "A_A") (pintype "passive"))
      (node (ref "LED8") (pin "C") (pinfunction "C_C") (pintype "passive"))
      (node (ref "R21") (pin "2") (pinfunction "2_2") (pintype "passive"))
    )
    (net (code "43") (name "Net-(LED11-PadC)") (class "Default")
      (node (ref "LED11") (pin "C") (pinfunction "C_C") (pintype "passive"))
      (node (ref "R23") (pin "2") (pinfunction "2_2") (pintype "passive"))
    )
    (net (code "44") (name "Net-(Q1-D)") (class "Default")
      (node (ref "F1") (pin "3") (pinfunction "2_3") (pintype "bidirectional"))
      (node (ref "F1") (pin "4") (pinfunction "2_4") (pintype "bidirectional"))
      (node (ref "Q1") (pin "4") (pinfunction "D_4") (pintype "bidirectional"))
      (node (ref "R1") (pin "2") (pinfunction "2_2") (pintype "passive"))
    )
    (net (code "45") (name "Net-(Q2-S)") (class "Default")
      (node (ref "Q2") (pin "3") (pinfunction "S_3") (pintype "bidirectional"))
      (node (ref "Q3") (pin "3") (pinfunction "S_3") (pintype "bidirectional"))
    )
    (net (code "46") (name "Net-(Q4-D)") (class "Default")
      (node (ref "C17") (pin "1") (pinfunction "1_1") (pintype "passive"))
      (node (ref "C18") (pin "+") (pinfunction "+_+") (pintype "bidirectional"))
      (node (ref "F7") (pin "2") (pinfunction "2_2") (pintype "bidirectional"))
      (node (ref "L1") (pin "2") (pinfunction "2_2") (pintype "bidirectional"))
      (node (ref "Q4") (pin "4") (pinfunction "D_4") (pintype "bidirectional"))
      (node (ref "VR1") (pin "2") (pinfunction "EN_2") (pintype "input"))
      (node (ref "VR1") (pin "4") (pinfunction "VIN_4") (pintype "input"))
    )
    (net (code "47") (name "Net-(Q4-G)") (class "Default")
      (node (ref "C5") (pin "2") (pinfunction "2_2") (pintype "passive"))
      (node (ref "CH4") (pin "2") (pinfunction "2_2") (pintype "bidirectional"))
      (node (ref "Q4") (pin "1") (pinfunction "G_1") (pintype "bidirectional"))
      (node (ref "R4") (pin "1") (pinfunction "1_1") (pintype "passive"))
    )
    (net (code "48") (name "Net-(Q5-D)") (class "Default")
      (node (ref "F4") (pin "1") (pinfunction "1_1") (pintype "bidirectional"))
      (node (ref "F4") (pin "2") (pinfunction "1_2") (pintype "bidirectional"))
      (node (ref "Q5") (pin "4") (pinfunction "D_4") (pintype "bidirectional"))
    )
    (net (code "49") (name "Net-(Q5-G)") (class "Default")
      (node (ref "C6") (pin "2") (pinfunction "2_2") (pintype "passive"))
      (node (ref "CH6") (pin "2") (pinfunction "2_2") (pintype "bidirectional"))
      (node (ref "Q5") (pin "1") (pinfunction "G_1") (pintype "bidirectional"))
      (node (ref "R5") (pin "1") (pinfunction "1_1") (pintype "passive"))
    )
    (net (code "50") (name "Net-(USB1-5V)") (class "Default")
      (node (ref "F6") (pin "2") (pinfunction "2_2") (pintype "bidirectional"))
      (node (ref "USB1") (pin "1") (pinfunction "5V_1") (pintype "bidirectional"))
    )
    (net (code "51") (name "Net-(VR1-FB)") (class "Default")
      (node (ref "R16") (pin "1") (pinfunction "1_1") (pintype "passive"))
      (node (ref "R17") (pin "2") (pinfunction "2_2") (pintype "passive"))
      (node (ref "VR1") (pin "5") (pinfunction "FB_5") (pintype "input"))
    )
    (net (code "52") (name "RS485_D+") (class "Default")
      (node (ref "CH10") (pin "3") (pinfunction "3_3") (pintype "bidirectional"))
      (node (ref "CH11") (pin "3") (pinfunction "3_3") (pintype "bidirectional"))
      (node (ref "CH12") (pin "3") (pinfunction "3_3") (pintype "bidirectional"))
      (node (ref "CH13") (pin "3") (pinfunction "3_3") (pintype "bidirectional"))
      (node (ref "CH8") (pin "3") (pinfunction "3_3") (pintype "bidirectional"))
      (node (ref "CH9") (pin "3") (pinfunction "3_3") (pintype "bidirectional"))
      (node (ref "D9") (pin "1") (pinfunction "1_1") (pintype "bidirectional"))
      (node (ref "IC3") (pin "6") (pinfunction "A_6") (pintype "bidirectional"))
      (node (ref "R12") (pin "1") (pinfunction "1_1") (pintype "passive"))
      (node (ref "R13") (pin "2") (pinfunction "2_2") (pintype "passive"))
    )
    (net (code "53") (name "RS485_D-") (class "Default")
      (node (ref "CH10") (pin "4") (pinfunction "4_4") (pintype "bidirectional"))
      (node (ref "CH11") (pin "4") (pinfunction "4_4") (pintype "bidirectional"))
      (node (ref "CH12") (pin "4") (pinfunction "4_4") (pintype "bidirectional"))
      (node (ref "CH13") (pin "4") (pinfunction "4_4") (pintype "bidirectional"))
      (node (ref "CH8") (pin "4") (pinfunction "4_4") (pintype "bidirectional"))
      (node (ref "CH9") (pin "4") (pinfunction "4_4") (pintype "bidirectional"))
      (node (ref "D8") (pin "1") (pinfunction "1_1") (pintype "bidirectional"))
      (node (ref "IC3") (pin "7") (pinfunction "B_7") (pintype "bidirectional"))
      (node (ref "R13") (pin "1") (pinfunction "1_1") (pintype "passive"))
      (node (ref "R14") (pin "2") (pinfunction "2_2") (pintype "passive"))
    )
    (net (code "54") (name "TF232RL_RX_LED") (class "Default")
      (node (ref "IC2") (pin "22") (pinfunction "CBUS1_22") (pintype "bidirectional"))
      (node (ref "R7") (pin "1") (pinfunction "1_1") (pintype "passive"))
    )
    (net (code "55") (name "USB-HUB_1_D+") (class "Default")
      (node (ref "IC1") (pin "11") (pinfunction "DP1_11") (pintype "bidirectional"))
      (node (ref "IC2") (pin "15") (pinfunction "USBDP_15") (pintype "bidirectional"))
    )
    (net (code "56") (name "USB-HUB_1_D-") (class "Default")
      (node (ref "IC1") (pin "10") (pinfunction "DM1_10") (pintype "bidirectional"))
      (node (ref "IC2") (pin "16") (pinfunction "USBDM_16") (pintype "bidirectional"))
    )
    (net (code "57") (name "USB-HUB_2_D+") (class "Default")
      (node (ref "D4") (pin "1") (pinfunction "1_1") (pintype "bidirectional"))
      (node (ref "IC1") (pin "9") (pinfunction "DP2_9") (pintype "bidirectional"))
      (node (ref "USB2") (pin "2") (pinfunction "A_D+_2") (pintype "bidirectional"))
    )
    (net (code "58") (name "USB-HUB_2_D-") (class "Default")
      (node (ref "D5") (pin "1") (pinfunction "1_1") (pintype "bidirectional"))
      (node (ref "IC1") (pin "8") (pinfunction "DM2_8") (pintype "bidirectional"))
      (node (ref "USB2") (pin "3") (pinfunction "A_D-_3") (pintype "bidirectional"))
    )
    (net (code "59") (name "USB-HUB_3_D+") (class "Default")
      (node (ref "D6") (pin "1") (pinfunction "1_1") (pintype "bidirectional"))
      (node (ref "IC1") (pin "7") (pinfunction "DP3_7") (pintype "bidirectional"))
      (node (ref "USB2") (pin "6") (pinfunction "B_D+_6") (pintype "bidirectional"))
    )
    (net (code "60") (name "USB-HUB_3_D-") (class "Default")
      (node (ref "D7") (pin "1") (pinfunction "1_1") (pintype "bidirectional"))
      (node (ref "IC1") (pin "6") (pinfunction "DM3_6") (pintype "bidirectional"))
      (node (ref "USB2") (pin "7") (pinfunction "B_D-_7") (pintype "bidirectional"))
    )
    (net (code "61") (name "USB_IN_D+") (class "Default")
      (node (ref "D2") (pin "1") (pinfunction "1_1") (pintype "bidirectional"))
      (node (ref "IC1") (pin "16") (pinfunction "DPU_16") (pintype "bidirectional"))
      (node (ref "USB1") (pin "3") (pinfunction "D+_3") (pintype "bidirectional"))
    )
    (net (code "62") (name "USB_IN_D-") (class "Default")
      (node (ref "D3") (pin "1") (pinfunction "1_1") (pintype "bidirectional"))
      (node (ref "IC1") (pin "15") (pinfunction "DMU_15") (pintype "bidirectional"))
      (node (ref "USB1") (pin "2") (pinfunction "D-_2") (pintype "bidirectional"))
    )
    (net (code "63") (name "VD18") (class "Default")
      (node (ref "C12") (pin "1") (pinfunction "1_1") (pintype "passive"))
      (node (ref "IC1") (pin "12") (pinfunction "VD18_O_12") (pintype "bidirectional"))
      (node (ref "IC1") (pin "28") (pinfunction "VD18_28") (pintype "bidirectional"))
    )
    (net (code "64") (name "VD33") (class "Default")
      (node (ref "C11") (pin "1") (pinfunction "1_1") (pintype "passive"))
      (node (ref "IC1") (pin "13") (pinfunction "VD33_13") (pintype "bidirectional"))
      (node (ref "IC1") (pin "17") (pinfunction "XRSTJ_17") (pintype "bidirectional"))
      (node (ref "IC1") (pin "18") (pinfunction "VBUSM_18") (pintype "bidirectional"))
      (node (ref "IC1") (pin "19") (pinfunction "BUSJ_19") (pintype "bidirectional"))
      (node (ref "IC1") (pin "21") (pinfunction "VD33_O_21") (pintype "bidirectional"))
      (node (ref "IC1") (pin "26") (pinfunction "OVCJ_26") (pintype "bidirectional"))
    )
    (net (code "65") (name "unconnected-(IC1-DM4-Pad4)") (class "Default")
      (node (ref "IC1") (pin "4") (pinfunction "DM4_4") (pintype "bidirectional"))
    )
    (net (code "66") (name "unconnected-(IC1-DP4-Pad5)") (class "Default")
      (node (ref "IC1") (pin "5") (pinfunction "DP4_5") (pintype "bidirectional"))
    )
    (net (code "67") (name "unconnected-(IC1-PWRJ-Pad25)") (class "Default")
      (node (ref "IC1") (pin "25") (pinfunction "PWRJ_25") (pintype "bidirectional"))
    )
    (net (code "68") (name "unconnected-(IC1-TESTJ-Pad27)") (class "Default")
      (node (ref "IC1") (pin "27") (pinfunction "TESTJ_27") (pintype "bidirectional"))
    )
    (net (code "69") (name "unconnected-(IC2-CBUS3-Pad14)") (class "Default")
      (node (ref "IC2") (pin "14") (pinfunction "CBUS3_14") (pintype "bidirectional"))
    )
    (net (code "70") (name "unconnected-(IC2-CBUS4-Pad12)") (class "Default")
      (node (ref "IC2") (pin "12") (pinfunction "CBUS4_12") (pintype "bidirectional"))
    )
    (net (code "71") (name "unconnected-(IC2-CTS#-Pad11)") (class "Default")
      (node (ref "IC2") (pin "11") (pinfunction "CTS#_11") (pintype "bidirectional"))
    )
    (net (code "72") (name "unconnected-(IC2-DCD#-Pad10)") (class "Default")
      (node (ref "IC2") (pin "10") (pinfunction "DCD#_10") (pintype "bidirectional"))
    )
    (net (code "73") (name "unconnected-(IC2-DSR#-Pad9)") (class "Default")
      (node (ref "IC2") (pin "9") (pinfunction "DSR#_9") (pintype "bidirectional"))
    )
    (net (code "74") (name "unconnected-(IC2-DTR#-Pad2)") (class "Default")
      (node (ref "IC2") (pin "2") (pinfunction "DTR#_2") (pintype "bidirectional"))
    )
    (net (code "75") (name "unconnected-(IC2-NC_1-Pad8)") (class "Default")
      (node (ref "IC2") (pin "8") (pinfunction "NC_1_8") (pintype "bidirectional"))
    )
    (net (code "76") (name "unconnected-(IC2-NC_2-Pad24)") (class "Default")
      (node (ref "IC2") (pin "24") (pinfunction "NC_2_24") (pintype "bidirectional"))
    )
    (net (code "77") (name "unconnected-(IC2-OSCI-Pad27)") (class "Default")
      (node (ref "IC2") (pin "27") (pinfunction "OSCI_27") (pintype "bidirectional"))
    )
    (net (code "78") (name "unconnected-(IC2-OSCO-Pad28)") (class "Default")
      (node (ref "IC2") (pin "28") (pinfunction "OSCO_28") (pintype "bidirectional"))
    )
    (net (code "79") (name "unconnected-(IC2-RESET#-Pad19)") (class "Default")
      (node (ref "IC2") (pin "19") (pinfunction "RESET#_19") (pintype "bidirectional"))
    )
    (net (code "80") (name "unconnected-(IC2-RI#-Pad6)") (class "Default")
      (node (ref "IC2") (pin "6") (pinfunction "RI#_6") (pintype "bidirectional"))
    )
    (net (code "81") (name "unconnected-(IC2-RTS#-Pad3)") (class "Default")
      (node (ref "IC2") (pin "3") (pinfunction "RTS#_3") (pintype "bidirectional"))
    )
    (net (code "82") (name "unconnected-(USB1-ID-Pad4)") (class "Default")
      (node (ref "USB1") (pin "4") (pinfunction "ID_4") (pintype "bidirectional"))
    )
  )
)
